# ne555_v1.net
KiCad netlist of a schematic drawn in EAGLE
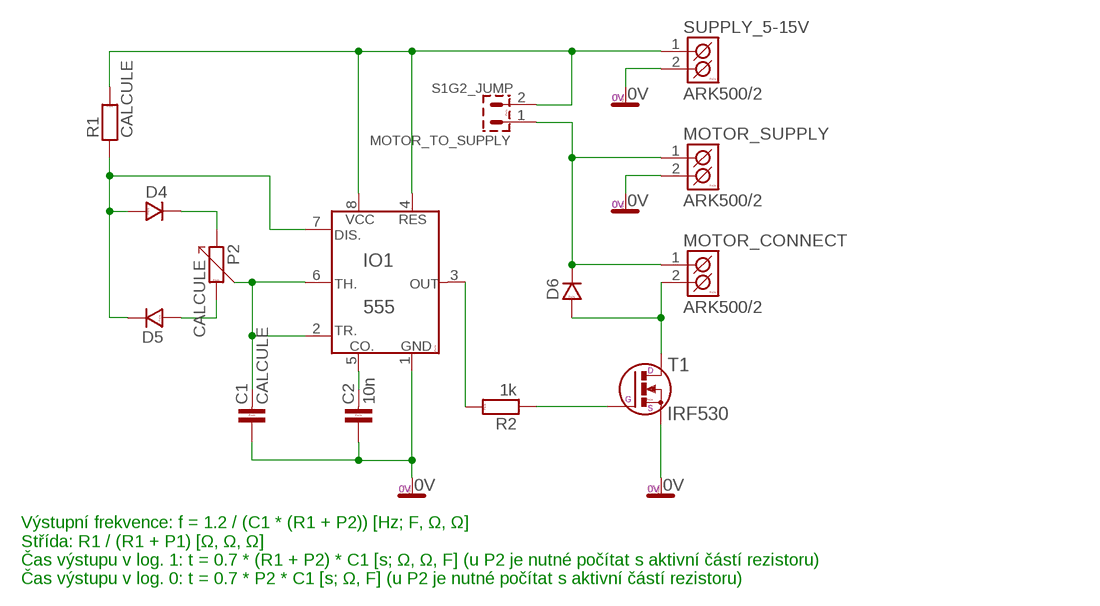
[diagram p0: schematic, sheet 1]

(export (version "E")
  (design (tool "Eeschema 10.0.6"))
  (components
    (comp (ref "C1")
      (value "CALCULE")
      (footprint "eagle-import:C-7,5")
      (libsource (lib "eagle-import") (part "C-KER_7,5"))
    )
    (comp (ref "C2")
      (value "10n")
      (footprint "eagle-import:C-7,5")
      (libsource (lib "eagle-import") (part "C-KER_7,5"))
    )
    (comp (ref "D4")
      (value "D_7,5")
      (footprint "eagle-import:DO35")
      (libsource (lib "eagle-import") (part "D_7,5"))
    )
    (comp (ref "D5")
      (value "D_7,5")
      (footprint "eagle-import:DO35")
      (libsource (lib "eagle-import") (part "D_7,5"))
    )
    (comp (ref "D6")
      (value "D_7,5")
      (footprint "eagle-import:DO35")
      (libsource (lib "eagle-import") (part "D_7,5"))
    )
    (comp (ref "IO1")
      (value "555")
      (footprint "eagle-import:DIL8")
      (libsource (lib "eagle-import") (part "555"))
    )
    (comp (ref "MOTOR_CONNECT")
      (value "ARK500/2")
      (footprint "eagle-import:ARK500_2")
      (libsource (lib "eagle-import") (part "ARK500/2"))
    )
    (comp (ref "MOTOR_SUPPLY")
      (value "ARK500/2")
      (footprint "eagle-import:ARK500_2")
      (libsource (lib "eagle-import") (part "ARK500/2"))
    )
    (comp (ref "MOTOR_TO_SUPPLY")
      (value "S1G2_JUMP")
      (footprint "eagle-import:S1G2_JUM")
      (libsource (lib "eagle-import") (part "S1G2_JUMP"))
    )
    (comp (ref "P2")
      (value "CALCULE")
      (footprint "eagle-import:PC16ML")
      (libsource (lib "eagle-import") (part "PC16ML"))
    )
    (comp (ref "R1")
      (value "CALCULE")
      (footprint "eagle-import:R-7,5")
      (libsource (lib "eagle-import") (part "R_7,5"))
    )
    (comp (ref "R2")
      (value "1k")
      (footprint "eagle-import:R-7,5")
      (libsource (lib "eagle-import") (part "R_7,5"))
    )
    (comp (ref "SUPPLY_5-15V")
      (value "ARK500/2")
      (footprint "eagle-import:ARK500_2")
      (libsource (lib "eagle-import") (part "ARK500/2"))
    )
    (comp (ref "T1")
      (value "IRF530")
      (footprint "eagle-import:TO-220S")
      (libsource (lib "eagle-import") (part "BUZ11"))
    )
  )
  (nets
    (net (code "1") (name "0V") (class "Default")
      (node (ref "C1") (pin "1") (pinfunction "1_1") (pintype "passive"))
      (node (ref "C2") (pin "1") (pinfunction "1_1") (pintype "passive"))
      (node (ref "IO1") (pin "1") (pinfunction "GND_1") (pintype "power_in"))
      (node (ref "MOTOR_SUPPLY") (pin "2") (pinfunction "K2_2") (pintype "passive"))
      (node (ref "SUPPLY_5-15V") (pin "2") (pinfunction "K2_2") (pintype "passive"))
      (node (ref "T1") (pin "3") (pinfunction "S_3") (pintype "passive"))
    )
    (net (code "2") (name "Net-(D4-PadK)") (class "Default")
      (node (ref "D4") (pin "K") (pinfunction "K_K") (pintype "passive"))
      (node (ref "P2") (pin "1") (pinfunction "1_1") (pintype "passive"))
    )
    (net (code "3") (name "Net-(D5-PadA)") (class "Default")
      (node (ref "D5") (pin "A") (pinfunction "A_A") (pintype "passive"))
      (node (ref "P2") (pin "2") (pinfunction "2_2") (pintype "passive"))
    )
    (net (code "4") (name "Net-(IO1-CO.)") (class "Default")
      (node (ref "C2") (pin "2") (pinfunction "2_2") (pintype "passive"))
      (node (ref "IO1") (pin "5") (pinfunction "CO._5") (pintype "input"))
    )
    (net (code "5") (name "Net-(IO1-DIS.)") (class "Default")
      (node (ref "D4") (pin "A") (pinfunction "A_A") (pintype "passive"))
      (node (ref "D5") (pin "K") (pinfunction "K_K") (pintype "passive"))
      (node (ref "IO1") (pin "7") (pinfunction "DIS._7") (pintype "input"))
      (node (ref "R1") (pin "1") (pinfunction "1_1") (pintype "passive"))
    )
    (net (code "6") (name "Net-(IO1-OUT)") (class "Default")
      (node (ref "IO1") (pin "3") (pinfunction "OUT_3") (pintype "output"))
      (node (ref "R2") (pin "2") (pinfunction "2_2") (pintype "passive"))
    )
    (net (code "7") (name "Net-(IO1-RES)") (class "Default")
      (node (ref "IO1") (pin "4") (pinfunction "RES_4") (pintype "input"))
      (node (ref "IO1") (pin "8") (pinfunction "VCC_8") (pintype "power_in"))
      (node (ref "MOTOR_TO_SUPPLY") (pin "2") (pinfunction "2_2") (pintype "passive"))
      (node (ref "R1") (pin "2") (pinfunction "2_2") (pintype "passive"))
      (node (ref "SUPPLY_5-15V") (pin "1") (pinfunction "K1_1") (pintype "passive"))
    )
    (net (code "8") (name "Net-(IO1-TH.)") (class "Default")
      (node (ref "C1") (pin "2") (pinfunction "2_2") (pintype "passive"))
      (node (ref "IO1") (pin "2") (pinfunction "TR._2") (pintype "input"))
      (node (ref "IO1") (pin "6") (pinfunction "TH._6") (pintype "input"))
      (node (ref "P2") (pin "3") (pinfunction "3_3") (pintype "passive"))
    )
    (net (code "9") (name "Net-(MOTOR_CONNECT-K1)") (class "Default")
      (node (ref "D6") (pin "K") (pinfunction "K_K") (pintype "passive"))
      (node (ref "MOTOR_CONNECT") (pin "1") (pinfunction "K1_1") (pintype "passive"))
      (node (ref "MOTOR_SUPPLY") (pin "1") (pinfunction "K1_1") (pintype "passive"))
      (node (ref "MOTOR_TO_SUPPLY") (pin "1") (pinfunction "1_1") (pintype "passive"))
    )
    (net (code "10") (name "Net-(MOTOR_CONNECT-K2)") (class "Default")
      (node (ref "D6") (pin "A") (pinfunction "A_A") (pintype "passive"))
      (node (ref "MOTOR_CONNECT") (pin "2") (pinfunction "K2_2") (pintype "passive"))
      (node (ref "T1") (pin "2") (pinfunction "D_2") (pintype "passive"))
    )
    (net (code "11") (name "Net-(T1-G)") (class "Default")
      (node (ref "R2") (pin "1") (pinfunction "1_1") (pintype "passive"))
      (node (ref "T1") (pin "1") (pinfunction "G_1") (pintype "passive"))
    )
  )
)
